# MCP73831T_LiPo_Charger.net
KiCad netlist of a schematic drawn in EAGLE
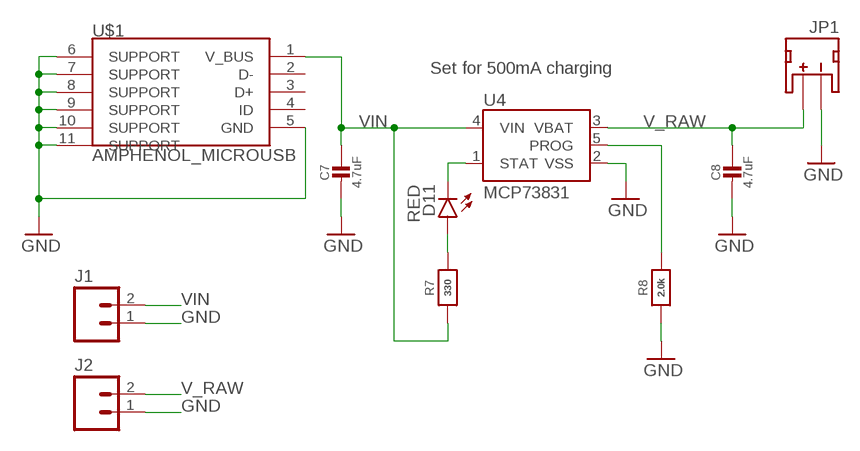
[diagram p0: schematic, sheet 1]

(export (version "E")
  (design (tool "Eeschema 10.0.6"))
  (components
    (comp (ref "C7")
      (value "4.7uF")
      (footprint "eagle-import:0805-NO")
      (libsource (lib "eagle-import") (part "CAP_CERAMIC0805-NOOUTLINE"))
    )
    (comp (ref "C8")
      (value "4.7uF")
      (footprint "eagle-import:0805-NO")
      (libsource (lib "eagle-import") (part "CAP_CERAMIC0805-NOOUTLINE"))
    )
    (comp (ref "D11")
      (value "RED")
      (footprint "eagle-import:LED-0603")
      (libsource (lib "eagle-import") (part "LED-RED0603"))
    )
    (comp (ref "J1")
      (value "M02PTH")
      (footprint "eagle-import:1X02")
      (libsource (lib "eagle-import") (part "M02PTH"))
    )
    (comp (ref "J2")
      (value "M02PTH")
      (footprint "eagle-import:1X02")
      (libsource (lib "eagle-import") (part "M02PTH"))
    )
    (comp (ref "JP1")
      (value "JST")
      (footprint "eagle-import:JST-2-SMD@1")
      (libsource (lib "eagle-import") (part "JST_2MM_MALE"))
    )
    (comp (ref "R7")
      (value "330")
      (footprint "eagle-import:_0805MP")
      (libsource (lib "eagle-import") (part "RESISTOR_0805MP"))
    )
    (comp (ref "R8")
      (value "2.0k")
      (footprint "eagle-import:_0805MP")
      (libsource (lib "eagle-import") (part "RESISTOR_0805MP"))
    )
    (comp (ref "U$1")
      (value "AMPHENOL_MICROUSB")
      (footprint "eagle-import:AMPHENOL_MICROUSB")
      (libsource (lib "eagle-import") (part "AMPHENOL_MICROUSB"))
    )
    (comp (ref "U4")
      (value "MCP73831")
      (footprint "eagle-import:SOT23-5")
      (libsource (lib "eagle-import") (part "MCP73831"))
    )
  )
  (nets
    (net (code "1") (name "/VIN") (class "Default")
      (node (ref "C7") (pin "1") (pinfunction "1_1") (pintype "passive"))
      (node (ref "J1") (pin "2") (pinfunction "2_2") (pintype "passive"))
      (node (ref "R7") (pin "1") (pinfunction "1_1") (pintype "passive"))
      (node (ref "U$1") (pin "1") (pinfunction "V_BUS_1") (pintype "bidirectional"))
      (node (ref "U4") (pin "4") (pinfunction "VIN_4") (pintype "power_in"))
    )
    (net (code "2") (name "/V_RAW") (class "Default")
      (node (ref "C8") (pin "1") (pinfunction "1_1") (pintype "passive"))
      (node (ref "J2") (pin "2") (pinfunction "2_2") (pintype "passive"))
      (node (ref "JP1") (pin "2") (pinfunction "+_2") (pintype "bidirectional"))
      (node (ref "U4") (pin "3") (pinfunction "VBAT_3") (pintype "power_in"))
    )
    (net (code "3") (name "GND") (class "Default")
      (node (ref "C7") (pin "2") (pinfunction "2_2") (pintype "passive"))
      (node (ref "C8") (pin "2") (pinfunction "2_2") (pintype "passive"))
      (node (ref "J1") (pin "1") (pinfunction "1_1") (pintype "passive"))
      (node (ref "J2") (pin "1") (pinfunction "1_1") (pintype "passive"))
      (node (ref "JP1") (pin "1") (pinfunction "-_1") (pintype "bidirectional"))
      (node (ref "R8") (pin "1") (pinfunction "1_1") (pintype "passive"))
      (node (ref "U$1") (pin "10") (pinfunction "SUPPORT_10") (pintype "bidirectional"))
      (node (ref "U$1") (pin "11") (pinfunction "SUPPORT_11") (pintype "bidirectional"))
      (node (ref "U$1") (pin "5") (pinfunction "GND_5") (pintype "bidirectional"))
      (node (ref "U$1") (pin "6") (pinfunction "SUPPORT_6") (pintype "bidirectional"))
      (node (ref "U$1") (pin "7") (pinfunction "SUPPORT_7") (pintype "bidirectional"))
      (node (ref "U$1") (pin "8") (pinfunction "SUPPORT_8") (pintype "bidirectional"))
      (node (ref "U$1") (pin "9") (pinfunction "SUPPORT_9") (pintype "bidirectional"))
      (node (ref "U4") (pin "2") (pinfunction "VSS_2") (pintype "power_in"))
    )
    (net (code "4") (name "Net-(D11-PadA)") (class "Default")
      (node (ref "D11") (pin "A") (pinfunction "A_A") (pintype "passive"))
      (node (ref "R7") (pin "2") (pinfunction "2_2") (pintype "passive"))
    )
    (net (code "5") (name "Net-(U4-PROG)") (class "Default")
      (node (ref "R8") (pin "2") (pinfunction "2_2") (pintype "passive"))
      (node (ref "U4") (pin "5") (pinfunction "PROG_5") (pintype "input"))
    )
    (net (code "6") (name "Net-(U4-STAT)") (class "Default")
      (node (ref "D11") (pin "C") (pinfunction "C_C") (pintype "passive"))
      (node (ref "U4") (pin "1") (pinfunction "STAT_1") (pintype "output"))
    )
    (net (code "7") (name "unconnected-(JP1-PAD1-PadNC1)") (class "Default")
      (node (ref "JP1") (pin "NC1") (pinfunction "PAD1_NC1") (pintype "bidirectional"))
    )
    (net (code "8") (name "unconnected-(JP1-PAD2-PadNC2)") (class "Default")
      (node (ref "JP1") (pin "NC2") (pinfunction "PAD2_NC2") (pintype "bidirectional"))
    )
    (net (code "9") (name "unconnected-(U$1-D+-Pad3)") (class "Default")
      (node (ref "U$1") (pin "3") (pinfunction "D+_3") (pintype "bidirectional"))
    )
    (net (code "10") (name "unconnected-(U$1-D--Pad2)") (class "Default")
      (node (ref "U$1") (pin "2") (pinfunction "D-_2") (pintype "bidirectional"))
    )
    (net (code "11") (name "unconnected-(U$1-ID-Pad4)") (class "Default")
      (node (ref "U$1") (pin "4") (pinfunction "ID_4") (pintype "bidirectional"))
    )
  )
)
